# AirScout_SchematicsV2_0.net
KiCad netlist of a schematic drawn in Altium Designer
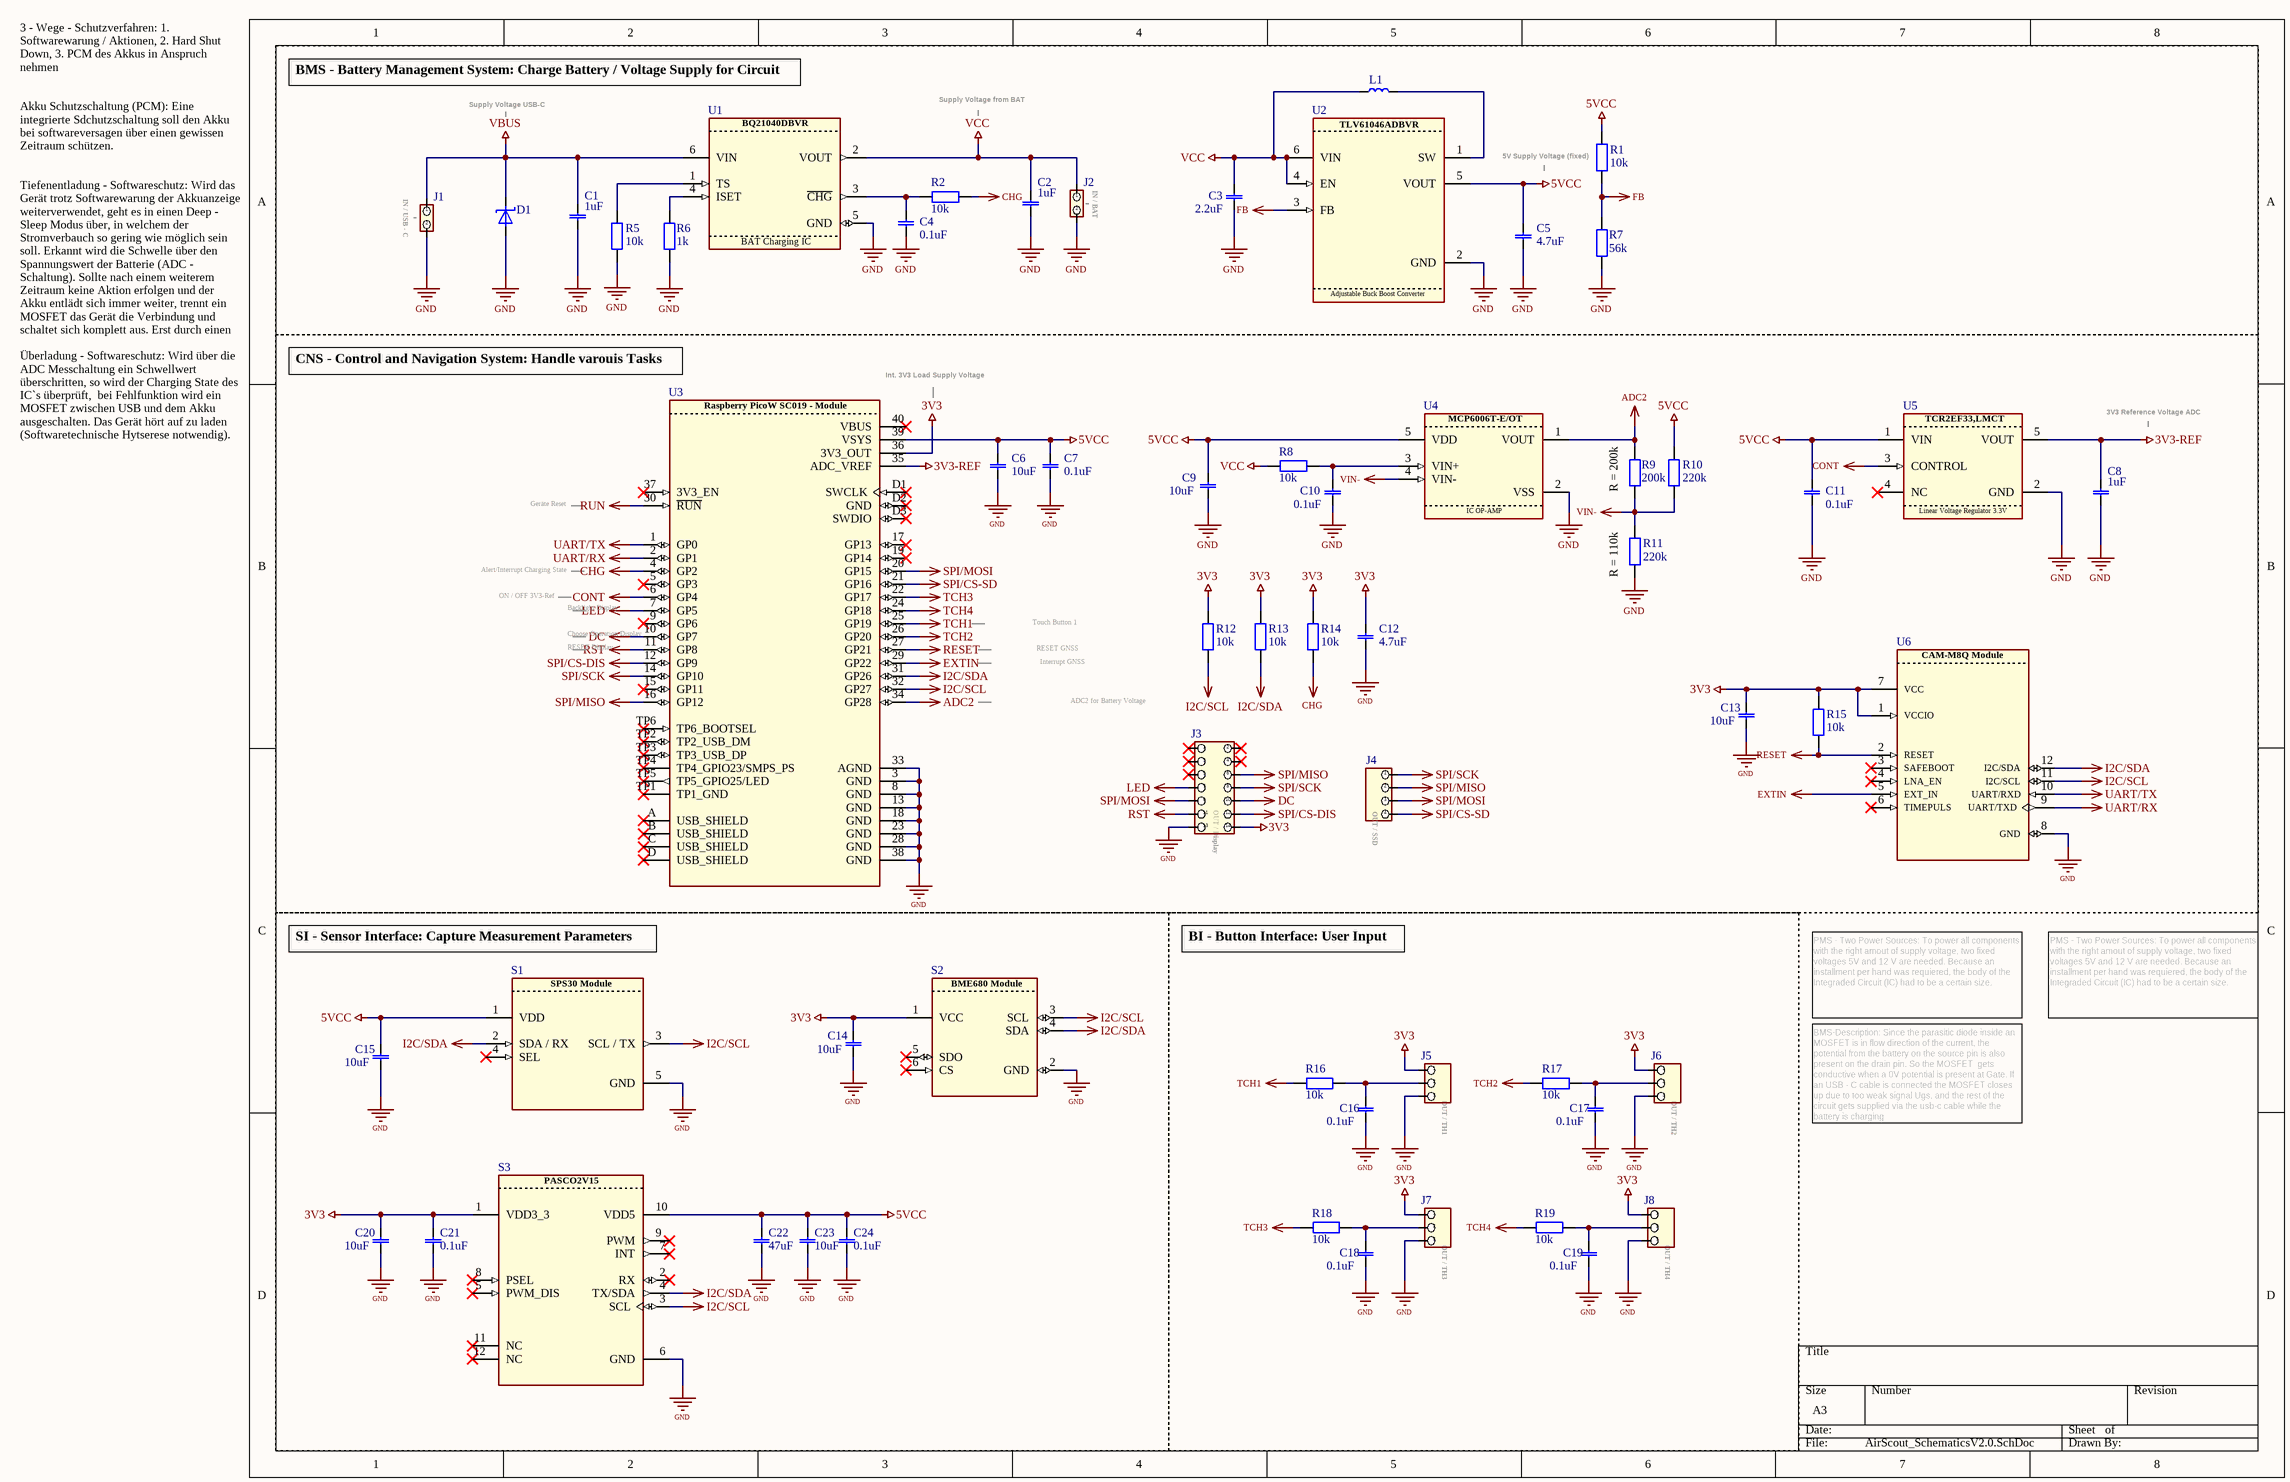
[diagram p0: AirScout_SchematicsV2.0.SchDoc]

(export (version "E")
  (design (tool "Eeschema 10.0.6"))
  (components
    (comp (ref "C1")
      (value "1uF")
      (footprint "CAPC340180_140N_KEM")
      (description "CAP CER 1UF 25V X7R 1206")
      (fields (field (name "Comment") "C1206C105K3RACTU"))
      (libsource (lib "AirScoutSchLibV2.0") (part "CAP"))
    )
    (comp (ref "C2")
      (value "1uF")
      (footprint "CAPC340180_140N_KEM")
      (description "CAP CER 1UF 25V X7R 1206")
      (fields (field (name "Comment") "C1206C105K3RACTU"))
      (libsource (lib "AirScoutSchLibV2.0") (part "CAP"))
    )
    (comp (ref "C3")
      (value "2.2uF")
      (footprint "CAPC340180_140N_KEM")
      (description "CAP CER 2.2UF 50V X7R 1206")
      (fields (field (name "Comment") "CL31B225KBHNNNE"))
      (libsource (lib "AirScoutSchLibV2.0") (part "CAP"))
    )
    (comp (ref "C4")
      (value "0.1uF")
      (footprint "CAPC340180_140N_KEM")
      (description "CAP CER 0.1UF 50V X7R 1206")
      (fields (field (name "Comment") "C1206C104K5RACTU"))
      (libsource (lib "AirScoutSchLibV2.0") (part "CAP"))
    )
    (comp (ref "C5")
      (value "4.7uF")
      (footprint "CAPC340180_140N_KEM")
      (description "CAP CER 4.7UF 50V X7R 1206")
      (fields (field (name "Comment") "CL31B475KBHNFNE"))
      (libsource (lib "AirScoutSchLibV2.0") (part "CAP"))
    )
    (comp (ref "C6")
      (value "10uF")
      (footprint "CAPC340180_140N_KEM")
      (description "CAP CER 10UF 25V X7R 1206")
      (fields (field (name "Comment") "CL31B106KAHNNNE"))
      (libsource (lib "AirScoutSchLibV2.0") (part "CAP"))
    )
    (comp (ref "C7")
      (value "0.1uF")
      (footprint "CAPC340180_140N_KEM")
      (description "CAP CER 0.1UF 50V X7R 1206")
      (fields (field (name "Comment") "C1206C104K5RACTU"))
      (libsource (lib "AirScoutSchLibV2.0") (part "CAP"))
    )
    (comp (ref "C8")
      (value "1uF")
      (footprint "CAPC340180_140N_KEM")
      (description "CAP CER 1UF 25V X7R 1206")
      (fields (field (name "Comment") "C1206C105K3RACTU"))
      (libsource (lib "AirScoutSchLibV2.0") (part "CAP"))
    )
    (comp (ref "C9")
      (value "10uF")
      (footprint "CAPC340180_140N_KEM")
      (description "CAP CER 10UF 25V X7R 1206")
      (fields (field (name "Comment") "CL31B106KAHNNNE"))
      (libsource (lib "AirScoutSchLibV2.0") (part "CAP"))
    )
    (comp (ref "C10")
      (value "0.1uF")
      (footprint "CAPC340180_140N_KEM")
      (description "CAP CER 0.1UF 50V X7R 1206")
      (fields (field (name "Comment") "C1206C104K5RACTU"))
      (libsource (lib "AirScoutSchLibV2.0") (part "CAP"))
    )
    (comp (ref "C11")
      (value "0.1uF")
      (footprint "CAPC340180_140N_KEM")
      (description "CAP CER 0.1UF 50V X7R 1206")
      (fields (field (name "Comment") "C1206C104K5RACTU"))
      (libsource (lib "AirScoutSchLibV2.0") (part "CAP"))
    )
    (comp (ref "C12")
      (value "4.7uF")
      (footprint "CAPC340180_140N_KEM")
      (description "CAP CER 4.7UF 50V X7R 1206")
      (fields (field (name "Comment") "CL31B475KBHNFNE"))
      (libsource (lib "AirScoutSchLibV2.0") (part "CAP"))
    )
    (comp (ref "C13")
      (value "10uF")
      (footprint "CAPC340180_140N_KEM")
      (description "CAP CER 10UF 25V X7R 1206")
      (fields (field (name "Comment") "CL31B106KAHNNNE"))
      (libsource (lib "AirScoutSchLibV2.0") (part "CAP"))
    )
    (comp (ref "C14")
      (value "10uF")
      (footprint "CAPC340180_140N_KEM")
      (description "CAP CER 10UF 25V X7R 1206")
      (fields (field (name "Comment") "CL31B106KAHNNNE"))
      (libsource (lib "AirScoutSchLibV2.0") (part "CAP"))
    )
    (comp (ref "C15")
      (value "10uF")
      (footprint "CAPC340180_140N_KEM")
      (description "CAP CER 10UF 25V X7R 1206")
      (fields (field (name "Comment") "CL31B106KAHNNNE"))
      (libsource (lib "AirScoutSchLibV2.0") (part "CAP"))
    )
    (comp (ref "C16")
      (value "0.1uF")
      (footprint "CAPC340180_140N_KEM")
      (description "CAP CER 0.1UF 50V X7R 1206")
      (fields (field (name "Comment") "C1206C104K5RACTU"))
      (libsource (lib "AirScoutSchLibV2.0") (part "CAP"))
    )
    (comp (ref "C17")
      (value "0.1uF")
      (footprint "CAPC340180_140N_KEM")
      (description "CAP CER 0.1UF 50V X7R 1206")
      (fields (field (name "Comment") "C1206C104K5RACTU"))
      (libsource (lib "AirScoutSchLibV2.0") (part "CAP"))
    )
    (comp (ref "C18")
      (value "0.1uF")
      (footprint "CAPC340180_140N_KEM")
      (description "CAP CER 0.1UF 50V X7R 1206")
      (fields (field (name "Comment") "C1206C104K5RACTU"))
      (libsource (lib "AirScoutSchLibV2.0") (part "CAP"))
    )
    (comp (ref "C19")
      (value "0.1uF")
      (footprint "CAPC340180_140N_KEM")
      (description "CAP CER 0.1UF 50V X7R 1206")
      (fields (field (name "Comment") "C1206C104K5RACTU"))
      (libsource (lib "AirScoutSchLibV2.0") (part "CAP"))
    )
    (comp (ref "C20")
      (value "10uF")
      (footprint "CAPC340180_140N_KEM")
      (description "CAP CER 10UF 25V X7R 1206")
      (fields (field (name "Comment") "CL31B106KAHNNNE"))
      (libsource (lib "AirScoutSchLibV2.0") (part "CAP"))
    )
    (comp (ref "C21")
      (value "0.1uF")
      (footprint "CAPC340180_140N_KEM")
      (description "CAP CER 0.1UF 50V X7R 1206")
      (fields (field (name "Comment") "C1206C104K5RACTU"))
      (libsource (lib "AirScoutSchLibV2.0") (part "CAP"))
    )
    (comp (ref "C22")
      (value "47uF")
      (footprint "CAPC340180_140N_KEM")
      (description "CAP CER 47UF 6.3V X5R 1206")
      (fields (field (name "Comment") "CL31A476MQHNNNE"))
      (libsource (lib "AirScoutSchLibV2.0") (part "CAP"))
    )
    (comp (ref "C23")
      (value "10uF")
      (footprint "CAPC340180_140N_KEM")
      (description "CAP CER 10UF 25V X7R 1206")
      (fields (field (name "Comment") "CL31B106KAHNNNE"))
      (libsource (lib "AirScoutSchLibV2.0") (part "CAP"))
    )
    (comp (ref "C24")
      (value "0.1uF")
      (footprint "CAPC340180_140N_KEM")
      (description "CAP CER 0.1UF 50V X7R 1206")
      (fields (field (name "Comment") "C1206C104K5RACTU"))
      (libsource (lib "AirScoutSchLibV2.0") (part "CAP"))
    )
    (comp (ref "D1")
      (value "SMBJ14CA-13-F")
      (footprint "SMB_DIO")
      (description "TVS DIODE 14VWM 23.2VC SMB")
      (libsource (lib "AirScoutSchLibV2.0") (part "Diode-Schottky"))
    )
    (comp (ref "J1")
      (value "B02B-PASK-1")
      (footprint "CONN_S2B-PH-K-S_JST")
      (description "CONN HEADER VERT 2POS 2MM")
      (libsource (lib "AirScoutSchLibV2.0") (part "CON2x1_vertical"))
    )
    (comp (ref "J2")
      (value "B02B-PASK-1")
      (footprint "CONN_S2B-PH-K-S_JST")
      (description "CONN HEADER VERT 2POS 2MM")
      (libsource (lib "AirScoutSchLibV2.0") (part "CON2x1_vertical"))
    )
    (comp (ref "J3")
      (value "IDMS-14-D-02.00-R")
      (footprint "CONN_14POL_SAMTEC")
      (description "Alternitives: IDMS-14-D-03.00, IDMS-14-D-02.00, IDMS-14-D-03.00-R")
      (libsource (lib "AirScoutSchLibV2.0") (part "CON7x2"))
    )
    (comp (ref "J4")
      (value "IDMS-4-D-02.00-R")
      (footprint "SAMTEC_IDMS-04-S-02.00")
      (description "Alternitives:  IDMS-4-D-03.00, IDMS-4-D-02.00, IDMS-4-D-03.00-R")
      (libsource (lib "AirScoutSchLibV2.0") (part "CON 4x1"))
    )
    (comp (ref "J5")
      (value "IDMS-3-D-02.00-R")
      (footprint "CONN_3POL_SAMTEC")
      (description "Alternitives:  IDMS-3-D-03.00, IDMS-3-D-02.00, IDMS-3-D-03.00-R")
      (libsource (lib "AirScoutSchLibV2.0") (part "CON 3x1"))
    )
    (comp (ref "J6")
      (value "IDMS-3-D-02.00-R")
      (footprint "CONN_3POL_SAMTEC")
      (description "Alternitives:  IDMS-3-D-03.00, IDMS-3-D-02.00, IDMS-3-D-03.00-R")
      (libsource (lib "AirScoutSchLibV2.0") (part "CON 3x1"))
    )
    (comp (ref "J7")
      (value "IDMS-3-D-02.00-R")
      (footprint "CONN_3POL_SAMTEC")
      (description "Alternitives:  IDMS-3-D-03.00, IDMS-3-D-02.00, IDMS-3-D-03.00-R")
      (libsource (lib "AirScoutSchLibV2.0") (part "CON 3x1"))
    )
    (comp (ref "J8")
      (value "IDMS-3-D-02.00-R")
      (footprint "CONN_3POL_SAMTEC")
      (description "Alternitives:  IDMS-3-D-03.00, IDMS-3-D-02.00, IDMS-3-D-03.00-R")
      (libsource (lib "AirScoutSchLibV2.0") (part "CON 3x1"))
    )
    (comp (ref "L1")
      (value "PA4332.103NLT")
      (footprint "IND_FDSD0420-H-100M=P3")
      (description "FIXED IND 10UH 2A 216 MOHM SMD; \r\nAIUR-05-100K")
      (libsource (lib "AirScoutSchLibV2.0") (part "Inductor"))
    )
    (comp (ref "R1")
      (value "10k")
      (footprint "RESC3116X65N")
      (description "RES 10K OHM 1% 1/4W 1206")
      (fields (field (name "Comment") "RC1206FR-0710KL"))
      (libsource (lib "AirScoutSchLibV2.0") (part "RES"))
    )
    (comp (ref "R2")
      (value "10k")
      (footprint "RESC3116X65N")
      (description "RES 10K OHM 1% 1/4W 1206")
      (fields (field (name "Comment") "RC1206FR-0710KL"))
      (libsource (lib "AirScoutSchLibV2.0") (part "RES"))
    )
    (comp (ref "R5")
      (value "10k")
      (footprint "RESC3116X65N")
      (description "RES 10K OHM 1% 1/4W 1206")
      (fields (field (name "Comment") "RC1206FR-0710KL"))
      (libsource (lib "AirScoutSchLibV2.0") (part "RES"))
    )
    (comp (ref "R6")
      (value "1k")
      (footprint "RESC3116X65N")
      (description "RES 1K OHM 1% 1/2W 1206")
      (fields (field (name "Comment") "RNCP1206FTD1K00"))
      (libsource (lib "AirScoutSchLibV2.0") (part "RES"))
    )
    (comp (ref "R7")
      (value "56k")
      (footprint "RESC3116X65N")
      (description "RES 56K OHM 5% 1/4W 1206")
      (fields (field (name "Comment") "RMCF1206JT56K0"))
      (libsource (lib "AirScoutSchLibV2.0") (part "RES"))
    )
    (comp (ref "R8")
      (value "10k")
      (footprint "RESC3116X65N")
      (description "RES 10K OHM 1% 1/4W 1206")
      (fields (field (name "Comment") "RC1206FR-0710KL"))
      (libsource (lib "AirScoutSchLibV2.0") (part "RES"))
    )
    (comp (ref "R9")
      (value "200k")
      (footprint "RESC3116X65N")
      (description "RES 200K OHM 5% 1/4W 1206")
      (fields (field (name "Comment") "RC1206JR-07200KL"))
      (libsource (lib "AirScoutSchLibV2.0") (part "RES"))
    )
    (comp (ref "R10")
      (value "220k")
      (footprint "RESC3116X65N")
      (description "RES 220K OHM 5% 1/4W 1206")
      (fields (field (name "Comment") "RC1206JR-07220KL"))
      (libsource (lib "AirScoutSchLibV2.0") (part "RES"))
    )
    (comp (ref "R11")
      (value "220k")
      (footprint "RESC3116X65N")
      (description "RES 220K OHM 5% 1/4W 1206")
      (fields (field (name "Comment") "RC1206JR-07220KL"))
      (libsource (lib "AirScoutSchLibV2.0") (part "RES"))
    )
    (comp (ref "R12")
      (value "10k")
      (footprint "RESC3116X65N")
      (description "RES 10K OHM 1% 1/4W 1206")
      (fields (field (name "Comment") "RC1206FR-0710KL"))
      (libsource (lib "AirScoutSchLibV2.0") (part "RES"))
    )
    (comp (ref "R13")
      (value "10k")
      (footprint "RESC3116X65N")
      (description "RES 10K OHM 1% 1/4W 1206")
      (fields (field (name "Comment") "RC1206FR-0710KL"))
      (libsource (lib "AirScoutSchLibV2.0") (part "RES"))
    )
    (comp (ref "R14")
      (value "10k")
      (footprint "RESC3116X65N")
      (description "RES 10K OHM 1% 1/4W 1206")
      (fields (field (name "Comment") "RC1206FR-0710KL"))
      (libsource (lib "AirScoutSchLibV2.0") (part "RES"))
    )
    (comp (ref "R15")
      (value "10k")
      (footprint "RESC3116X65N")
      (description "RES 10K OHM 1% 1/4W 1206")
      (fields (field (name "Comment") "RC1206FR-0710KL"))
      (libsource (lib "AirScoutSchLibV2.0") (part "RES"))
    )
    (comp (ref "R16")
      (value "10k")
      (footprint "RESC3116X65N")
      (description "RES 10K OHM 1% 1/4W 1206")
      (fields (field (name "Comment") "RC1206FR-0710KL"))
      (libsource (lib "AirScoutSchLibV2.0") (part "RES"))
    )
    (comp (ref "R17")
      (value "10k")
      (footprint "RESC3116X65N")
      (description "RES 10K OHM 1% 1/4W 1206")
      (fields (field (name "Comment") "RC1206FR-0710KL"))
      (libsource (lib "AirScoutSchLibV2.0") (part "RES"))
    )
    (comp (ref "R18")
      (value "10k")
      (footprint "RESC3116X65N")
      (description "RES 10K OHM 1% 1/4W 1206")
      (fields (field (name "Comment") "RC1206FR-0710KL"))
      (libsource (lib "AirScoutSchLibV2.0") (part "RES"))
    )
    (comp (ref "R19")
      (value "10k")
      (footprint "RESC3116X65N")
      (description "RES 10K OHM 1% 1/4W 1206")
      (fields (field (name "Comment") "RC1206FR-0710KL"))
      (libsource (lib "AirScoutSchLibV2.0") (part "RES"))
    )
    (comp (ref "S1")
      (value "B5B-ZR")
      (footprint "CONN5_B5B-ZR_JST")
      (description "Plug: CONN HEADER VERT 5POS 1.5MM; Air Sensor Dust Sensor Box SPS30 Module: 1649-1106-ND")
      (libsource (lib "AirScoutSchLibV2.0") (part "SPS30 Module"))
    )
    (comp (ref "S2")
      (value "NPPC061KFXC-RC")
      (footprint "PIM357")
      (libsource (lib "AirScoutSchLibV2.0") (part "BME680 Module"))
    )
    (comp (ref "S3")
      (value "NPPC061KFXC-RC")
      (footprint "IFX-SMD-LG-MLGA-14-1-V_MODUL")
      (description "(2x) CONN RCPT 6POS 0.1 GOLD SMD; Sensor: EVALCO25VMINIBOARDTOBO1; EVAL BOARD")
      (libsource (lib "AirScoutSchLibV2.0") (part "PASCO2V15 Module"))
    )
    (comp (ref "U1")
      (value "BQ21040DBVR")
      (footprint "SOT95P280X145-6N")
      (fields (field (name "MF") "Texas Instruments"))
      (libsource (lib "AirScoutSchLibV2.0") (part "BQ21040DBVR"))
    )
    (comp (ref "U2")
      (value "TLV61046ADBVR")
      (footprint "DBV0006A_M")
      (description "28-V Output Voltage Boost Converter with Power Diode and Isolation Switch 6-SOT-23 -40 to 125")
      (fields (field (name "COPYRIGHT") "Copyright (C) 2025 Ultra Librarian. All rights reserved."))
      (libsource (lib "AirScoutSchLibV2.0") (part "TLV61046ADBVR"))
    )
    (comp (ref "U3")
      (value "SSM-120-L-SV-BE-K-TR")
      (footprint "PicoW SC019")
      (description "(2x) CONN RCPT 20POS 0.1 GOLD SMD; PicoW: SC0918; RASPBERRY PI PICO W RP2040")
      (libsource (lib "AirScoutSchLibV2.0") (part "Raspberry PicoW SC019 Module"))
    )
    (comp (ref "U4")
      (value "MCP6006T-E/OT")
      (footprint "SOT23-5-AP2202K_DIO-M")
      (description "IC OPAMP GP 1 CIRCUIT SOT23-5")
      (libsource (lib "AirScoutSchLibV2.0") (part "MCP6006T-E/OT"))
    )
    (comp (ref "U5")
      (value "TCR2EF33,LM(CT")
      (footprint "SOT-25   SMV_TOS")
      (description "IC REG LINEAR 3.3V 200MA SMV")
      (fields (field (name "COPYRIGHT") "Copyright (C) 2025 Ultra Librarian. All rights reserved."))
      (libsource (lib "AirScoutSchLibV2.0") (part "TCR2EF33,LMCT"))
    )
    (comp (ref "U6")
      (value "NPPC061KFXC-RC")
      (footprint "CAM8MQ-Mod")
      (description "(2x) CONN HDR 6POS 0.1 GOLD SMD; GPS - Module:  201880; CAM-M8Q-BREAKOUT MULTI GNSS MODU")
      (libsource (lib "AirScoutSchLibV2.0") (part "CAM-M8Q Module"))
    )
  )
  (nets
    (net (code "1") (name "3V3") (class "Default")
      (node (ref "C12") (pin "2") (pinfunction "2_2") (pintype "passive"))
      (node (ref "C13") (pin "2") (pinfunction "2_2") (pintype "passive"))
      (node (ref "C14") (pin "2") (pinfunction "2_2") (pintype "passive"))
      (node (ref "C20") (pin "2") (pinfunction "2_2") (pintype "passive"))
      (node (ref "C21") (pin "2") (pinfunction "2_2") (pintype "passive"))
      (node (ref "J3") (pin "14") (pinfunction "14_14") (pintype "passive"))
      (node (ref "J5") (pin "1") (pinfunction "1_1") (pintype "passive"))
      (node (ref "J6") (pin "1") (pinfunction "1_1") (pintype "passive"))
      (node (ref "J7") (pin "1") (pinfunction "1_1") (pintype "passive"))
      (node (ref "J8") (pin "1") (pinfunction "1_1") (pintype "passive"))
      (node (ref "R12") (pin "2") (pinfunction "2_2") (pintype "passive"))
      (node (ref "R13") (pin "2") (pinfunction "2_2") (pintype "passive"))
      (node (ref "R14") (pin "2") (pinfunction "2_2") (pintype "passive"))
      (node (ref "R15") (pin "2") (pinfunction "2_2") (pintype "passive"))
      (node (ref "S2") (pin "1") (pinfunction "VCC_1") (pintype "power_in"))
      (node (ref "S3") (pin "1") (pinfunction "VDD3_3_1") (pintype "power_in"))
      (node (ref "U3") (pin "36") (pinfunction "3V3_OUT_36") (pintype "power_in"))
      (node (ref "U6") (pin "1") (pinfunction "VCCIO_1") (pintype "input"))
      (node (ref "U6") (pin "7") (pinfunction "VCC_7") (pintype "power_in"))
    )
    (net (code "2") (name "3V3-REF") (class "Default")
      (node (ref "C8") (pin "2") (pinfunction "2_2") (pintype "passive"))
      (node (ref "U3") (pin "35") (pinfunction "ADC_VREF_35") (pintype "power_in"))
      (node (ref "U5") (pin "5") (pinfunction "VOUT_5") (pintype "power_in"))
    )
    (net (code "3") (name "5VCC") (class "Default")
      (node (ref "C11") (pin "2") (pinfunction "2_2") (pintype "passive"))
      (node (ref "C15") (pin "2") (pinfunction "2_2") (pintype "passive"))
      (node (ref "C22") (pin "2") (pinfunction "2_2") (pintype "passive"))
      (node (ref "C23") (pin "2") (pinfunction "2_2") (pintype "passive"))
      (node (ref "C24") (pin "2") (pinfunction "2_2") (pintype "passive"))
      (node (ref "C5") (pin "2") (pinfunction "2_2") (pintype "passive"))
      (node (ref "C6") (pin "2") (pinfunction "2_2") (pintype "passive"))
      (node (ref "C7") (pin "2") (pinfunction "2_2") (pintype "passive"))
      (node (ref "C9") (pin "2") (pinfunction "2_2") (pintype "passive"))
      (node (ref "R1") (pin "2") (pinfunction "2_2") (pintype "passive"))
      (node (ref "R10") (pin "2") (pinfunction "2_2") (pintype "passive"))
      (node (ref "S1") (pin "1") (pinfunction "VDD_1") (pintype "passive"))
      (node (ref "S3") (pin "10") (pinfunction "VDD5_10") (pintype "power_in"))
      (node (ref "U2") (pin "5") (pinfunction "VOUT_5") (pintype "power_in"))
      (node (ref "U3") (pin "39") (pinfunction "VSYS_39") (pintype "power_in"))
      (node (ref "U4") (pin "5") (pinfunction "VDD_5") (pintype "power_in"))
      (node (ref "U5") (pin "1") (pinfunction "VIN_1") (pintype "power_in"))
    )
    (net (code "4") (name "ADC2") (class "Default")
      (node (ref "R9") (pin "2") (pinfunction "2_2") (pintype "passive"))
      (node (ref "U3") (pin "34") (pinfunction "GP28_34") (pintype "bidirectional"))
      (node (ref "U4") (pin "1") (pinfunction "VOUT_1") (pintype "power_in"))
    )
    (net (code "5") (name "CHG") (class "Default")
      (node (ref "R14") (pin "1") (pinfunction "1_1") (pintype "passive"))
      (node (ref "R2") (pin "1") (pinfunction "1_1") (pintype "passive"))
      (node (ref "U3") (pin "4") (pinfunction "GP2_4") (pintype "bidirectional"))
    )
    (net (code "6") (name "CONT") (class "Default")
      (node (ref "U3") (pin "6") (pinfunction "GP4_6") (pintype "bidirectional"))
      (node (ref "U5") (pin "3") (pinfunction "CONTROL_3") (pintype "input"))
    )
    (net (code "7") (name "DC") (class "Default")
      (node (ref "J3") (pin "10") (pinfunction "10_10") (pintype "passive"))
      (node (ref "U3") (pin "10") (pinfunction "GP7_10") (pintype "bidirectional"))
    )
    (net (code "8") (name "EXTIN") (class "Default")
      (node (ref "U3") (pin "29") (pinfunction "GP22_29") (pintype "bidirectional"))
      (node (ref "U6") (pin "5") (pinfunction "EXT_IN_5") (pintype "input"))
    )
    (net (code "9") (name "FB") (class "Default")
      (node (ref "R1") (pin "1") (pinfunction "1_1") (pintype "passive"))
      (node (ref "R7") (pin "2") (pinfunction "2_2") (pintype "passive"))
      (node (ref "U2") (pin "3") (pinfunction "FB_3") (pintype "input"))
    )
    (net (code "10") (name "GND") (class "Default")
      (node (ref "C1") (pin "1") (pinfunction "1_1") (pintype "passive"))
      (node (ref "C10") (pin "1") (pinfunction "1_1") (pintype "passive"))
      (node (ref "C11") (pin "1") (pinfunction "1_1") (pintype "passive"))
      (node (ref "C12") (pin "1") (pinfunction "1_1") (pintype "passive"))
      (node (ref "C13") (pin "1") (pinfunction "1_1") (pintype "passive"))
      (node (ref "C14") (pin "1") (pinfunction "1_1") (pintype "passive"))
      (node (ref "C15") (pin "1") (pinfunction "1_1") (pintype "passive"))
      (node (ref "C16") (pin "1") (pinfunction "1_1") (pintype "passive"))
      (node (ref "C17") (pin "1") (pinfunction "1_1") (pintype "passive"))
      (node (ref "C18") (pin "1") (pinfunction "1_1") (pintype "passive"))
      (node (ref "C19") (pin "1") (pinfunction "1_1") (pintype "passive"))
      (node (ref "C2") (pin "1") (pinfunction "1_1") (pintype "passive"))
      (node (ref "C20") (pin "1") (pinfunction "1_1") (pintype "passive"))
      (node (ref "C21") (pin "1") (pinfunction "1_1") (pintype "passive"))
      (node (ref "C22") (pin "1") (pinfunction "1_1") (pintype "passive"))
      (node (ref "C23") (pin "1") (pinfunction "1_1") (pintype "passive"))
      (node (ref "C24") (pin "1") (pinfunction "1_1") (pintype "passive"))
      (node (ref "C3") (pin "1") (pinfunction "1_1") (pintype "passive"))
      (node (ref "C4") (pin "1") (pinfunction "1_1") (pintype "passive"))
      (node (ref "C5") (pin "1") (pinfunction "1_1") (pintype "passive"))
      (node (ref "C6") (pin "1") (pinfunction "1_1") (pintype "passive"))
      (node (ref "C7") (pin "1") (pinfunction "1_1") (pintype "passive"))
      (node (ref "C8") (pin "1") (pinfunction "1_1") (pintype "passive"))
      (node (ref "C9") (pin "1") (pinfunction "1_1") (pintype "passive"))
      (node (ref "D1") (pin "A") (pinfunction "A_A") (pintype "passive"))
      (node (ref "J1") (pin "2") (pinfunction "-_2") (pintype "passive"))
      (node (ref "J2") (pin "2") (pinfunction "-_2") (pintype "passive"))
      (node (ref "J3") (pin "13") (pinfunction "13_13") (pintype "passive"))
      (node (ref "J5") (pin "3") (pinfunction "3_3") (pintype "passive"))
      (node (ref "J6") (pin "3") (pinfunction "3_3") (pintype "passive"))
      (node (ref "J7") (pin "3") (pinfunction "3_3") (pintype "passive"))
      (node (ref "J8") (pin "3") (pinfunction "3_3") (pintype "passive"))
      (node (ref "R11") (pin "1") (pinfunction "1_1") (pintype "passive"))
      (node (ref "R5") (pin "1") (pinfunction "1_1") (pintype "passive"))
      (node (ref "R6") (pin "1") (pinfunction "1_1") (pintype "passive"))
      (node (ref "R7") (pin "1") (pinfunction "1_1") (pintype "passive"))
      (node (ref "S1") (pin "5") (pinfunction "GND_5") (pintype "passive"))
      (node (ref "S2") (pin "2") (pinfunction "GND_2") (pintype "bidirectional"))
      (node (ref "S3") (pin "6") (pinfunction "GND_6") (pintype "power_in"))
      (node (ref "U1") (pin "5") (pinfunction "GND_5") (pintype "bidirectional"))
      (node (ref "U2") (pin "2") (pinfunction "GND_2") (pintype "power_in"))
      (node (ref "U3") (pin "13") (pinfunction "GND_13") (pintype "power_in"))
      (node (ref "U3") (pin "18") (pinfunction "GND_18") (pintype "power_in"))
      (node (ref "U3") (pin "23") (pinfunction "GND_23") (pintype "power_in"))
      (node (ref "U3") (pin "28") (pinfunction "GND_28") (pintype "power_in"))
      (node (ref "U3") (pin "3") (pinfunction "GND_3") (pintype "power_in"))
      (node (ref "U3") (pin "33") (pinfunction "AGND_33") (pintype "power_in"))
      (node (ref "U3") (pin "38") (pinfunction "GND_38") (pintype "power_in"))
      (node (ref "U3") (pin "8") (pinfunction "GND_8") (pintype "power_in"))
      (node (ref "U4") (pin "2") (pinfunction "VSS_2") (pintype "power_in"))
      (node (ref "U5") (pin "2") (pinfunction "GND_2") (pintype "power_in"))
      (node (ref "U6") (pin "8") (pinfunction "GND_8") (pintype "bidirectional"))
    )
    (net (code "11") (name "I2C{slash}SCL") (class "Default")
      (node (ref "R12") (pin "1") (pinfunction "1_1") (pintype "passive"))
      (node (ref "S1") (pin "3") (pinfunction "SCL_/_TX_3") (pintype "output"))
      (node (ref "S2") (pin "3") (pinfunction "SCL_3") (pintype "bidirectional"))
      (node (ref "S3") (pin "3") (pinfunction "SCL_3") (pintype "bidirectional"))
      (node (ref "U3") (pin "32") (pinfunction "GP27_32") (pintype "bidirectional"))
      (node (ref "U6") (pin "11") (pinfunction "I2C/SCL_11") (pintype "bidirectional"))
    )
    (net (code "12") (name "I2C{slash}SDA") (class "Default")
      (node (ref "R13") (pin "1") (pinfunction "1_1") (pintype "passive"))
      (node (ref "S1") (pin "2") (pinfunction "SDA_/_RX_2") (pintype "input"))
      (node (ref "S2") (pin "4") (pinfunction "SDA_4") (pintype "bidirectional"))
      (node (ref "S3") (pin "4") (pinfunction "TX/SDA_4") (pintype "output"))
      (node (ref "U3") (pin "31") (pinfunction "GP26_31") (pintype "bidirectional"))
      (node (ref "U6") (pin "12") (pinfunction "I2C/SDA_12") (pintype "bidirectional"))
    )
    (net (code "13") (name "LED") (class "Default")
      (node (ref "J3") (pin "7") (pinfunction "7_7") (pintype "passive"))
      (node (ref "U3") (pin "7") (pinfunction "GP5_7") (pintype "bidirectional"))
    )
    (net (code "14") (name "Net-(C16-Pad2)") (class "Default")
      (node (ref "C16") (pin "2") (pinfunction "2_2") (pintype "passive"))
      (node (ref "J5") (pin "2") (pinfunction "2_2") (pintype "passive"))
      (node (ref "R16") (pin "1") (pinfunction "1_1") (pintype "passive"))
    )
    (net (code "15") (name "Net-(C17-Pad2)") (class "Default")
      (node (ref "C17") (pin "2") (pinfunction "2_2") (pintype "passive"))
      (node (ref "J6") (pin "2") (pinfunction "2_2") (pintype "passive"))
      (node (ref "R17") (pin "1") (pinfunction "1_1") (pintype "passive"))
    )
    (net (code "16") (name "Net-(C18-Pad2)") (class "Default")
      (node (ref "C18") (pin "2") (pinfunction "2_2") (pintype "passive"))
      (node (ref "J7") (pin "2") (pinfunction "2_2") (pintype "passive"))
      (node (ref "R18") (pin "1") (pinfunction "1_1") (pintype "passive"))
    )
    (net (code "17") (name "Net-(C19-Pad2)") (class "Default")
      (node (ref "C19") (pin "2") (pinfunction "2_2") (pintype "passive"))
      (node (ref "J8") (pin "2") (pinfunction "2_2") (pintype "passive"))
      (node (ref "R19") (pin "1") (pinfunction "1_1") (pintype "passive"))
    )
    (net (code "18") (name "Net-(U1-ISET)") (class "Default")
      (node (ref "R6") (pin "2") (pinfunction "2_2") (pintype "passive"))
      (node (ref "U1") (pin "4") (pinfunction "ISET_4") (pintype "input"))
    )
    (net (code "19") (name "Net-(U1-TS)") (class "Default")
      (node (ref "R5") (pin "2") (pinfunction "2_2") (pintype "passive"))
      (node (ref "U1") (pin "1") (pinfunction "TS_1") (pintype "input"))
    )
    (net (code "20") (name "Net-(U1-~{CHG})") (class "Default")
      (node (ref "C4") (pin "2") (pinfunction "2_2") (pintype "passive"))
      (node (ref "R2") (pin "2") (pinfunction "2_2") (pintype "passive"))
      (node (ref "U1") (pin "3") (pinfunction "~{CHG}_3") (pintype "output"))
    )
    (net (code "21") (name "Net-(U2-SW)") (class "Default")
      (node (ref "L1") (pin "2") (pinfunction "2_2") (pintype "passive"))
      (node (ref "U2") (pin "1") (pinfunction "SW_1") (pintype "power_in"))
    )
    (net (code "22") (name "Net-(U4-VIN+)") (class "Default")
      (node (ref "C10") (pin "2") (pinfunction "2_2") (pintype "passive"))
      (node (ref "R8") (pin "1") (pinfunction "1_1") (pintype "passive"))
      (node (ref "U4") (pin "3") (pinfunction "VIN+_3") (pintype "input"))
    )
    (net (code "23") (name "RESET") (class "Default")
      (node (ref "R15") (pin "1") (pinfunction "1_1") (pintype "passive"))
      (node (ref "U3") (pin "27") (pinfunction "GP21_27") (pintype "bidirectional"))
      (node (ref "U6") (pin "2") (pinfunction "RESET_2") (pintype "input"))
    )
    (net (code "24") (name "RST") (class "Default")
      (node (ref "J3") (pin "11") (pinfunction "11_11") (pintype "passive"))
      (node (ref "U3") (pin "11") (pinfunction "GP8_11") (pintype "bidirectional"))
    )
    (net (code "25") (name "RUN") (class "Default")
      (node (ref "U3") (pin "30") (pinfunction "~{RUN}_30") (pintype "input"))
    )
    (net (code "26") (name "SPI{slash}CS-DIS") (class "Default")
      (node (ref "J3") (pin "12") (pinfunction "12_12") (pintype "passive"))
      (node (ref "U3") (pin "12") (pinfunction "GP9_12") (pintype "bidirectional"))
    )
    (net (code "27") (name "SPI{slash}CS-SD") (class "Default")
      (node (ref "J4") (pin "4") (pinfunction "4_4") (pintype "passive"))
      (node (ref "U3") (pin "21") (pinfunction "GP16_21") (pintype "bidirectional"))
    )
    (net (code "28") (name "SPI{slash}MISO") (class "Default")
      (node (ref "J3") (pin "6") (pinfunction "6_6") (pintype "passive"))
      (node (ref "J4") (pin "2") (pinfunction "2_2") (pintype "passive"))
      (node (ref "U3") (pin "16") (pinfunction "GP12_16") (pintype "bidirectional"))
    )
    (net (code "29") (name "SPI{slash}MOSI") (class "Default")
      (node (ref "J3") (pin "9") (pinfunction "9_9") (pintype "passive"))
      (node (ref "J4") (pin "3") (pinfunction "3_3") (pintype "passive"))
      (node (ref "U3") (pin "20") (pinfunction "GP15_20") (pintype "bidirectional"))
    )
    (net (code "30") (name "SPI{slash}SCK") (class "Default")
      (node (ref "J3") (pin "8") (pinfunction "8_8") (pintype "passive"))
      (node (ref "J4") (pin "1") (pinfunction "1_1") (pintype "passive"))
      (node (ref "U3") (pin "14") (pinfunction "GP10_14") (pintype "bidirectional"))
    )
    (net (code "31") (name "TCH1") (class "Default")
      (node (ref "R16") (pin "2") (pinfunction "2_2") (pintype "passive"))
      (node (ref "U3") (pin "25") (pinfunction "GP19_25") (pintype "bidirectional"))
    )
    (net (code "32") (name "TCH2") (class "Default")
      (node (ref "R17") (pin "2") (pinfunction "2_2") (pintype "passive"))
      (node (ref "U3") (pin "26") (pinfunction "GP20_26") (pintype "bidirectional"))
    )
    (net (code "33") (name "TCH3") (class "Default")
      (node (ref "R18") (pin "2") (pinfunction "2_2") (pintype "passive"))
      (node (ref "U3") (pin "22") (pinfunction "GP17_22") (pintype "bidirectional"))
    )
    (net (code "34") (name "TCH4") (class "Default")
      (node (ref "R19") (pin "2") (pinfunction "2_2") (pintype "passive"))
      (node (ref "U3") (pin "24") (pinfunction "GP18_24") (pintype "bidirectional"))
    )
    (net (code "35") (name "UART{slash}RX") (class "Default")
      (node (ref "U3") (pin "2") (pinfunction "GP1_2") (pintype "bidirectional"))
      (node (ref "U6") (pin "9") (pinfunction "UART/TXD_9") (pintype "output"))
    )
    (net (code "36") (name "UART{slash}TX") (class "Default")
      (node (ref "U3") (pin "1") (pinfunction "GP0_1") (pintype "bidirectional"))
      (node (ref "U6") (pin "10") (pinfunction "UART/RXD_10") (pintype "input"))
    )
    (net (code "37") (name "VBUS") (class "Default")
      (node (ref "C1") (pin "2") (pinfunction "2_2") (pintype "passive"))
      (node (ref "D1") (pin "K") (pinfunction "K_K") (pintype "passive"))
      (node (ref "J1") (pin "1") (pinfunction "+_1") (pintype "passive"))
      (node (ref "U1") (pin "6") (pinfunction "VIN_6") (pintype "power_in"))
    )
    (net (code "38") (name "VCC") (class "Default")
      (node (ref "C2") (pin "2") (pinfunction "2_2") (pintype "passive"))
      (node (ref "C3") (pin "2") (pinfunction "2_2") (pintype "passive"))
      (node (ref "J2") (pin "1") (pinfunction "+_1") (pintype "passive"))
      (node (ref "L1") (pin "1") (pinfunction "1_1") (pintype "passive"))
      (node (ref "R8") (pin "2") (pinfunction "2_2") (pintype "passive"))
      (node (ref "U1") (pin "2") (pinfunction "VOUT_2") (pintype "output"))
      (node (ref "U2") (pin "4") (pinfunction "EN_4") (pintype "input"))
      (node (ref "U2") (pin "6") (pinfunction "VIN_6") (pintype "power_in"))
    )
    (net (code "39") (name "VIN-") (class "Default")
      (node (ref "R10") (pin "1") (pinfunction "1_1") (pintype "passive"))
      (node (ref "R11") (pin "2") (pinfunction "2_2") (pintype "passive"))
      (node (ref "R9") (pin "1") (pinfunction "1_1") (pintype "passive"))
      (node (ref "U4") (pin "4") (pinfunction "VIN-_4") (pintype "input"))
    )
    (net (code "40") (name "unconnected-(J3-Pad1)") (class "Default")
      (node (ref "J3") (pin "1") (pinfunction "1_1") (pintype "passive+no_connect"))
    )
    (net (code "41") (name "unconnected-(J3-Pad2)") (class "Default")
      (node (ref "J3") (pin "2") (pinfunction "2_2") (pintype "passive+no_connect"))
    )
    (net (code "42") (name "unconnected-(J3-Pad3)") (class "Default")
      (node (ref "J3") (pin "3") (pinfunction "3_3") (pintype "passive+no_connect"))
    )
    (net (code "43") (name "unconnected-(J3-Pad4)") (class "Default")
      (node (ref "J3") (pin "4") (pinfunction "4_4") (pintype "passive+no_connect"))
    )
    (net (code "44") (name "unconnected-(J3-Pad5)") (class "Default")
      (node (ref "J3") (pin "5") (pinfunction "5_5") (pintype "passive+no_connect"))
    )
    (net (code "45") (name "unconnected-(S1-SEL-Pad4)") (class "Default")
      (node (ref "S1") (pin "4") (pinfunction "SEL_4") (pintype "input+no_connect"))
    )
    (net (code "46") (name "unconnected-(S2-CS-Pad6)") (class "Default")
      (node (ref "S2") (pin "6") (pinfunction "CS_6") (pintype "input+no_connect"))
    )
    (net (code "47") (name "unconnected-(S2-SDO-Pad5)") (class "Default")
      (node (ref "S2") (pin "5") (pinfunction "SDO_5") (pintype "bidirectional+no_connect"))
    )
    (net (code "48") (name "unconnected-(S3-INT-Pad7)") (class "Default")
      (node (ref "S3") (pin "7") (pinfunction "INT_7") (pintype "output+no_connect"))
    )
    (net (code "49") (name "unconnected-(S3-NC-Pad11)") (class "Default")
      (node (ref "S3") (pin "11") (pinfunction "NC_11") (pintype "power_in+no_connect"))
    )
    (net (code "50") (name "unconnected-(S3-NC-Pad12)") (class "Default")
      (node (ref "S3") (pin "12") (pinfunction "NC_12") (pintype "passive+no_connect"))
    )
    (net (code "51") (name "unconnected-(S3-PSEL-Pad8)") (class "Default")
      (node (ref "S3") (pin "8") (pinfunction "PSEL_8") (pintype "input+no_connect"))
    )
    (net (code "52") (name "unconnected-(S3-PWM-Pad9)") (class "Default")
      (node (ref "S3") (pin "9") (pinfunction "PWM_9") (pintype "output+no_connect"))
    )
    (net (code "53") (name "unconnected-(S3-PWM_DIS-Pad5)") (class "Default")
      (node (ref "S3") (pin "5") (pinfunction "PWM_DIS_5") (pintype "input+no_connect"))
    )
    (net (code "54") (name "unconnected-(S3-RX-Pad2)") (class "Default")
      (node (ref "S3") (pin "2") (pinfunction "RX_2") (pintype "bidirectional+no_connect"))
    )
    (net (code "55") (name "unconnected-(U3-3V3_EN-Pad37)") (class "Default")
      (node (ref "U3") (pin "37") (pinfunction "3V3_EN_37") (pintype "input+no_connect"))
    )
    (net (code "56") (name "unconnected-(U3-GND-PadD2)") (class "Default")
      (node (ref "U3") (pin "D2") (pinfunction "GND_D2") (pintype "bidirectional+no_connect"))
    )
    (net (code "57") (name "unconnected-(U3-GP3-Pad5)") (class "Default")
      (node (ref "U3") (pin "5") (pinfunction "GP3_5") (pintype "bidirectional+no_connect"))
    )
    (net (code "58") (name "unconnected-(U3-GP6-Pad9)") (class "Default")
      (node (ref "U3") (pin "9") (pinfunction "GP6_9") (pintype "bidirectional+no_connect"))
    )
    (net (code "59") (name "unconnected-(U3-GP11-Pad15)") (class "Default")
      (node (ref "U3") (pin "15") (pinfunction "GP11_15") (pintype "bidirectional+no_connect"))
    )
    (net (code "60") (name "unconnected-(U3-GP13-Pad17)") (class "Default")
      (node (ref "U3") (pin "17") (pinfunction "GP13_17") (pintype "bidirectional+no_connect"))
    )
    (net (code "61") (name "unconnected-(U3-GP14-Pad19)") (class "Default")
      (node (ref "U3") (pin "19") (pinfunction "GP14_19") (pintype "bidirectional+no_connect"))
    )
    (net (code "62") (name "unconnected-(U3-SWCLK-PadD1)") (class "Default")
      (node (ref "U3") (pin "D1") (pinfunction "SWCLK_D1") (pintype "input+no_connect"))
    )
    (net (code "63") (name "unconnected-(U3-SWDIO-PadD3)") (class "Default")
      (node (ref "U3") (pin "D3") (pinfunction "SWDIO_D3") (pintype "bidirectional+no_connect"))
    )
    (net (code "64") (name "unconnected-(U3-TP1_GND-PadTP1)") (class "Default")
      (node (ref "U3") (pin "TP1") (pinfunction "TP1_GND_TP1") (pintype "power_in+no_connect"))
    )
    (net (code "65") (name "unconnected-(U3-TP2_USB_DM-PadTP2)") (class "Default")
      (node (ref "U3") (pin "TP2") (pinfunction "TP2_USB_DM_TP2") (pintype "bidirectional+no_connect"))
    )
    (net (code "66") (name "unconnected-(U3-TP3_USB_DP-PadTP3)") (class "Default")
      (node (ref "U3") (pin "TP3") (pinfunction "TP3_USB_DP_TP3") (pintype "bidirectional+no_connect"))
    )
    (net (code "67") (name "unconnected-(U3-TP4_GPIO23{slash}SMPS_PS-PadTP4)") (class "Default")
      (node (ref "U3") (pin "TP4") (pinfunction "TP4_GPIO23/SMPS_PS_TP4") (pintype "passive+no_connect"))
    )
    (net (code "68") (name "unconnected-(U3-TP5_GPIO25{slash}LED-PadTP5)") (class "Default")
      (node (ref "U3") (pin "TP5") (pinfunction "TP5_GPIO25/LED_TP5") (pintype "output+no_connect"))
    )
    (net (code "69") (name "unconnected-(U3-TP6_BOOTSEL-PadTP6)") (class "Default")
      (node (ref "U3") (pin "TP6") (pinfunction "TP6_BOOTSEL_TP6") (pintype "input+no_connect"))
    )
    (net (code "70") (name "unconnected-(U3-USB_SHIELD-PadA)") (class "Default")
      (node (ref "U3") (pin "A") (pinfunction "USB_SHIELD_A") (pintype "power_in+no_connect"))
    )
    (net (code "71") (name "unconnected-(U3-USB_SHIELD-PadB)") (class "Default")
      (node (ref "U3") (pin "B") (pinfunction "USB_SHIELD_B") (pintype "power_in+no_connect"))
    )
    (net (code "72") (name "unconnected-(U3-USB_SHIELD-PadC)") (class "Default")
      (node (ref "U3") (pin "C") (pinfunction "USB_SHIELD_C") (pintype "power_in+no_connect"))
    )
    (net (code "73") (name "unconnected-(U3-USB_SHIELD-PadD)") (class "Default")
      (node (ref "U3") (pin "D") (pinfunction "USB_SHIELD_D") (pintype "power_in+no_connect"))
    )
    (net (code "74") (name "unconnected-(U3-VBUS-Pad40)") (class "Default")
      (node (ref "U3") (pin "40") (pinfunction "VBUS_40") (pintype "power_in+no_connect"))
    )
    (net (code "75") (name "unconnected-(U5-NC-Pad4)") (class "Default")
      (node (ref "U5") (pin "4") (pinfunction "NC_4") (pintype "passive+no_connect"))
    )
    (net (code "76") (name "unconnected-(U6-LNA_EN-Pad4)") (class "Default")
      (node (ref "U6") (pin "4") (pinfunction "LNA_EN_4") (pintype "input+no_connect"))
    )
    (net (code "77") (name "unconnected-(U6-SAFEBOOT-Pad3)") (class "Default")
      (node (ref "U6") (pin "3") (pinfunction "SAFEBOOT_3") (pintype "input+no_connect"))
    )
    (net (code "78") (name "unconnected-(U6-TIMEPULS-Pad6)") (class "Default")
      (node (ref "U6") (pin "6") (pinfunction "TIMEPULS_6") (pintype "input+no_connect"))
    )
  )
)
